# simple_led_button.net
KiCad netlist of a schematic drawn in EAGLE
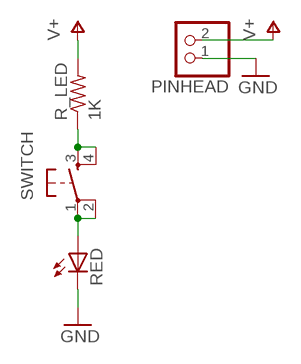
[diagram p0: schematic, sheet 1]

(export (version "E")
  (design (tool "Eeschema 10.0.6"))
  (components
    (comp (ref "PINHEAD")
      (value "PINHD-1X2")
      (footprint "eagle-import:1X02")
      (libsource (lib "eagle-import") (part "PINHD-1X2"))
    )
    (comp (ref "RED")
      (value "LEDFAB1206")
      (footprint "eagle-import:LED1206FAB")
      (libsource (lib "eagle-import") (part "LEDFAB1206"))
    )
    (comp (ref "R_LED")
      (value "1K")
      (footprint "eagle-import:R1206FAB")
      (libsource (lib "eagle-import") (part "RES-US1206FAB"))
    )
    (comp (ref "SWITCH")
      (value "6MM_SWITCH6MM_SWITCH")
      (footprint "eagle-import:6MM_SWITCH")
      (libsource (lib "eagle-import") (part "6MM_SWITCH6MM_SWITCH"))
    )
  )
  (nets
    (net (code "1") (name "GND") (class "Default")
      (node (ref "PINHEAD") (pin "1") (pinfunction "1_1") (pintype "passive"))
      (node (ref "RED") (pin "2") (pinfunction "C_2") (pintype "passive"))
    )
    (net (code "2") (name "Net-(RED-A)") (class "Default")
      (node (ref "RED") (pin "1") (pinfunction "A_1") (pintype "passive"))
      (node (ref "SWITCH") (pin "1") (pinfunction "P_1") (pintype "passive"))
      (node (ref "SWITCH") (pin "2") (pinfunction "P1_2") (pintype "passive"))
    )
    (net (code "3") (name "Net-(SWITCH-S)") (class "Default")
      (node (ref "R_LED") (pin "1") (pinfunction "1_1") (pintype "passive"))
      (node (ref "SWITCH") (pin "3") (pinfunction "S_3") (pintype "passive"))
      (node (ref "SWITCH") (pin "4") (pinfunction "S1_4") (pintype "passive"))
    )
    (net (code "4") (name "V+") (class "Default")
      (node (ref "PINHEAD") (pin "2") (pinfunction "2_2") (pintype "passive"))
      (node (ref "R_LED") (pin "2") (pinfunction "2_2") (pintype "passive"))
    )
  )
)
